# ProPrj_LED__2025-12-11-22-40-32.net
KiCad netlist of a schematic drawn in EasyEDA Pro
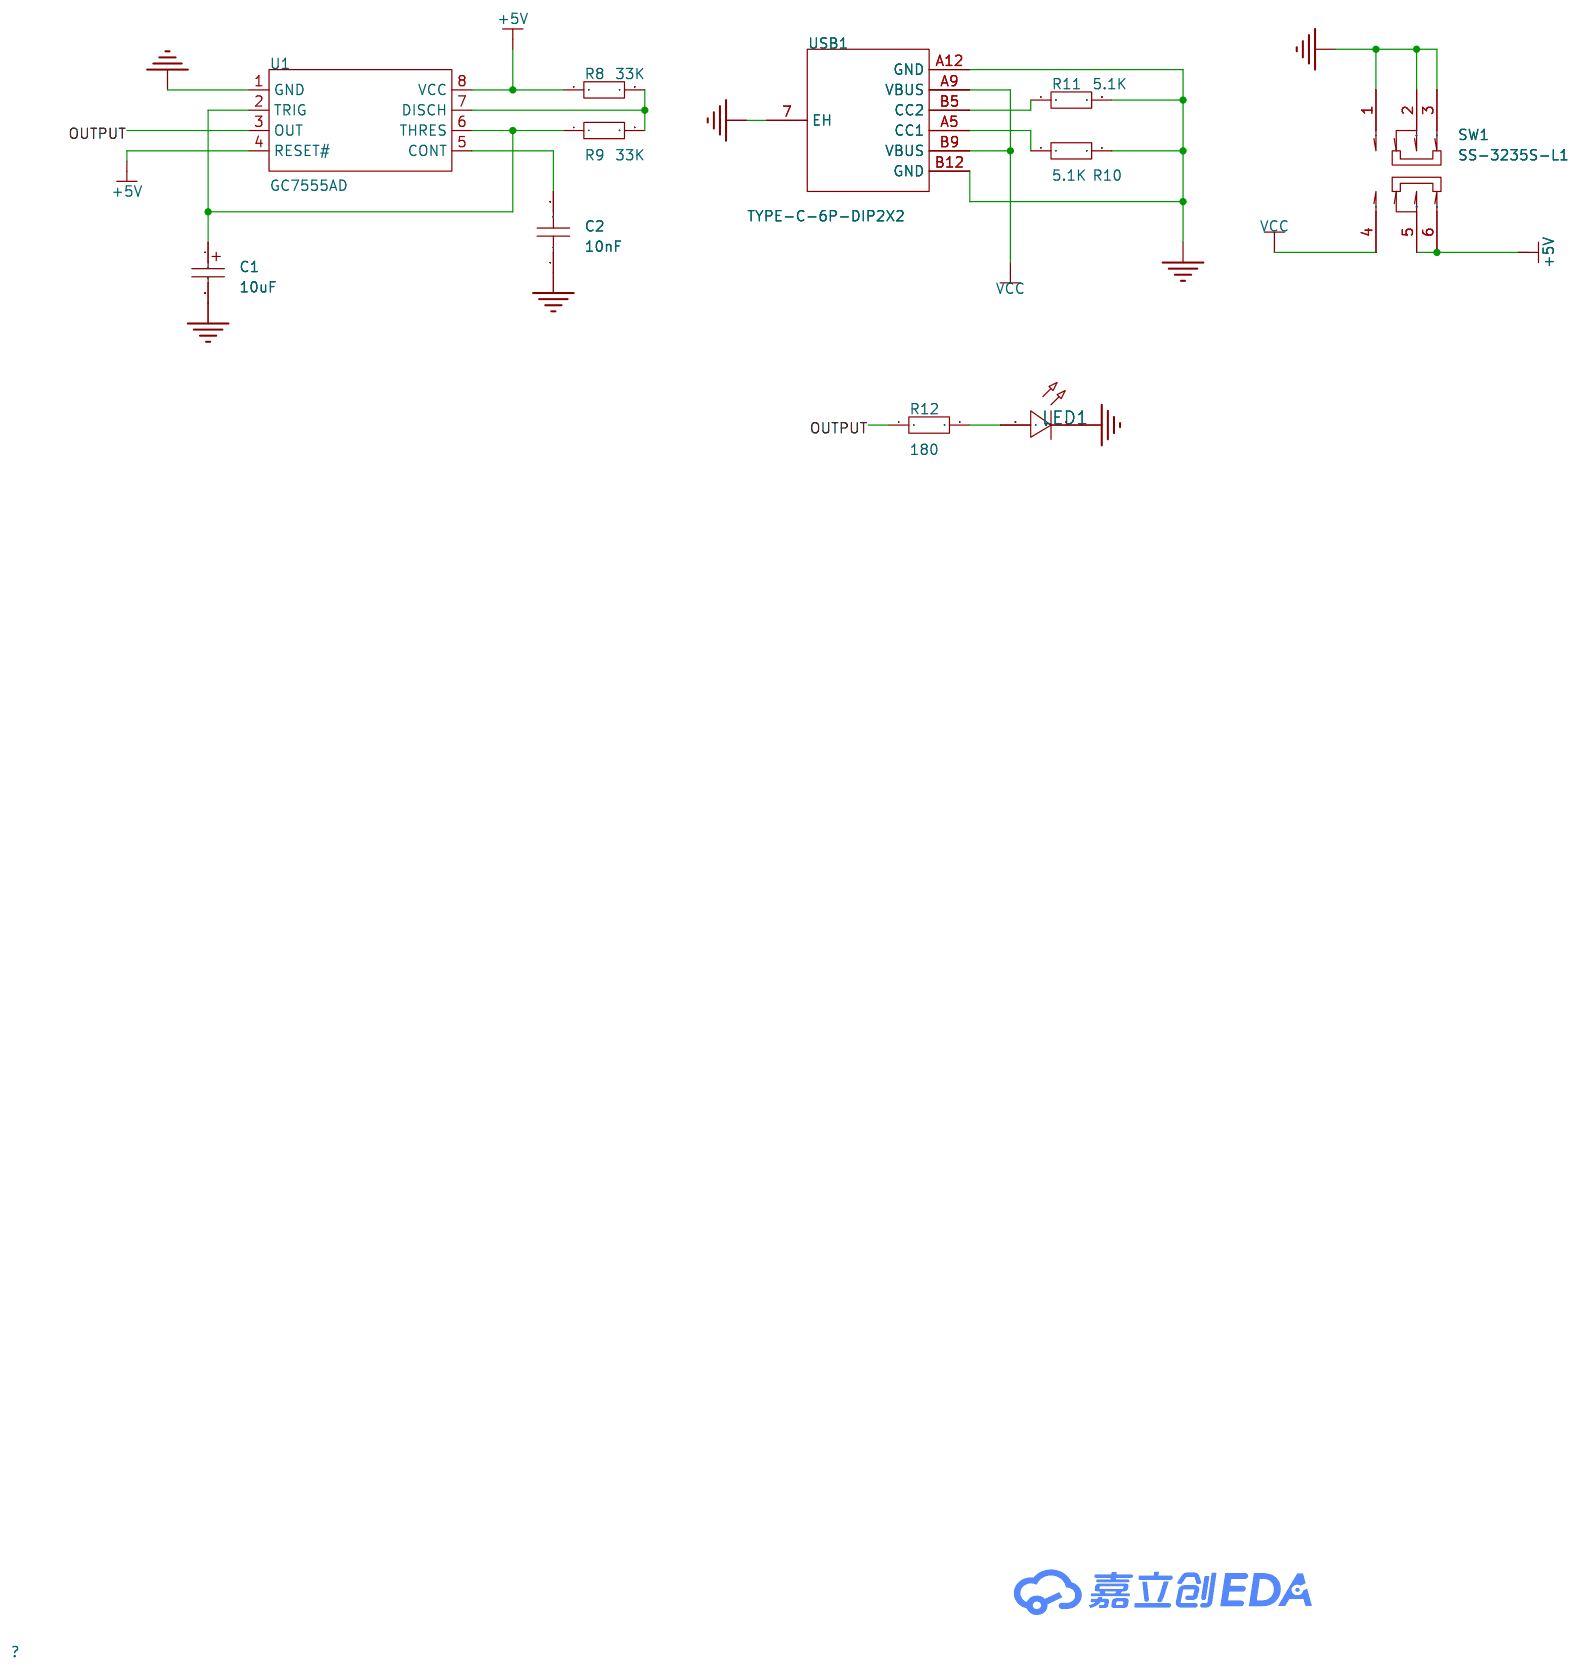
[diagram p0: schematic sheet]

(export (version "E")
  (design (tool "Eeschema 10.0.6"))
  (components
    (comp (ref "C1")
      (value "10uF")
      (footprint "easyedapro:C_Ele_SMD_3x5.4mm")
      (libsource (lib "easyedapro") (part "CAP"))
    )
    (comp (ref "C2")
      (value "10nF")
      (footprint "easyedapro:C0603")
      (libsource (lib "easyedapro") (part "Capacitance"))
    )
    (comp (ref "LED1")
      (value "~")
      (footprint "easyedapro:LED_0603")
      (libsource (lib "easyedapro") (part "LED_R"))
    )
    (comp (ref "R8") (value "33K") (footprint "easyedapro:R0805") (libsource (lib "easyedapro") (part "电阻")))
    (comp (ref "R9") (value "33K") (footprint "easyedapro:R0805") (libsource (lib "easyedapro") (part "电阻")))
    (comp (ref "R10")
      (value "5.1K")
      (footprint "easyedapro:R0805")
      (libsource (lib "easyedapro") (part "电阻"))
    )
    (comp (ref "R11")
      (value "5.1K")
      (footprint "easyedapro:R0805")
      (libsource (lib "easyedapro") (part "电阻"))
    )
    (comp (ref "R12") (value "180") (footprint "easyedapro:R0805") (libsource (lib "easyedapro") (part "电阻")))
    (comp (ref "SW1")
      (value "SS-3235S-L1")
      (footprint "easyedapro:SW-SMD_SS-3235S-LX")
      (description "电路结构:双刀双掷;安装方式:卧贴;开关颜色:黑色;额定电流:50mA;额定电压:12V;工作寿命:1万次;")
      (fields (field (name "Manufacturer") "XKB Connection(中国星坤)"))
      (libsource (lib "easyedapro") (part "SS-3235S-L1"))
    )
    (comp (ref "U1")
      (value "GC7555AD")
      (footprint "easyedapro:PDIP-8_L9.5-W6.4-P2.54-LS7.6-BL")
      (description "通用计时器：时基电路；计时；脉冲产生；满足用户（至少工业级）自主可控的需求。")
      (fields (field (name "Manufacturer") "Sungine(双竞集成)"))
      (libsource (lib "easyedapro") (part "GC7555AD"))
    )
    (comp (ref "USB1")
      (value "TYPE-C-6P-DIP2X2")
      (footprint "easyedapro:TYPE-C-SMD_TYPE-C-6P")
      (libsource (lib "easyedapro") (part "TYPE-C-6P-DIP2X2"))
    )
  )
  (nets
    (net (code "1") (name "+5V") (class "Default")
      (node (ref "R8") (pin "1") (pinfunction "1_1") (pintype "input"))
      (node (ref "SW1") (pin "5") (pinfunction "5_5") (pintype "unspecified"))
      (node (ref "SW1") (pin "6") (pinfunction "6_6") (pintype "unspecified"))
      (node (ref "U1") (pin "4") (pinfunction "RESET#_4") (pintype "unspecified"))
      (node (ref "U1") (pin "8") (pinfunction "VCC_8") (pintype "unspecified"))
    )
    (net (code "2") (name "/OUTPUT") (class "Default")
      (node (ref "R12") (pin "1") (pinfunction "1_1") (pintype "input"))
      (node (ref "U1") (pin "3") (pinfunction "OUT_3") (pintype "unspecified"))
    )
    (net (code "3") (name "GND") (class "Default")
      (node (ref "C1") (pin "2") (pinfunction "2_2") (pintype "input"))
      (node (ref "C2") (pin "1") (pinfunction "1_1") (pintype "input"))
      (node (ref "LED1") (pin "1") (pinfunction "C_1") (pintype "input"))
      (node (ref "R10") (pin "2") (pinfunction "2_2") (pintype "input"))
      (node (ref "R11") (pin "2") (pinfunction "2_2") (pintype "input"))
      (node (ref "SW1") (pin "1") (pinfunction "1_1") (pintype "unspecified"))
      (node (ref "SW1") (pin "2") (pinfunction "2_2") (pintype "unspecified"))
      (node (ref "SW1") (pin "3") (pinfunction "3_3") (pintype "unspecified"))
      (node (ref "U1") (pin "1") (pinfunction "GND_1") (pintype "unspecified"))
      (node (ref "USB1") (pin "7") (pinfunction "EH_7") (pintype "unspecified"))
      (node (ref "USB1") (pin "A12") (pinfunction "GND_A12") (pintype "unspecified"))
      (node (ref "USB1") (pin "B12") (pinfunction "GND_B12") (pintype "unspecified"))
    )
    (net (code "4") (name "Net-(LED1-A)") (class "Default")
      (node (ref "LED1") (pin "2") (pinfunction "A_2") (pintype "input"))
      (node (ref "R12") (pin "2") (pinfunction "2_2") (pintype "input"))
    )
    (net (code "5") (name "Net-(U1-CONT)") (class "Default")
      (node (ref "C2") (pin "2") (pinfunction "2_2") (pintype "input"))
      (node (ref "U1") (pin "5") (pinfunction "CONT_5") (pintype "unspecified"))
    )
    (net (code "6") (name "Net-(U1-DISCH)") (class "Default")
      (node (ref "R8") (pin "2") (pinfunction "2_2") (pintype "input"))
      (node (ref "R9") (pin "2") (pinfunction "2_2") (pintype "input"))
      (node (ref "U1") (pin "7") (pinfunction "DISCH_7") (pintype "unspecified"))
    )
    (net (code "7") (name "Net-(U1-THRES)") (class "Default")
      (node (ref "C1") (pin "1") (pinfunction "1_1") (pintype "input"))
      (node (ref "R9") (pin "1") (pinfunction "1_1") (pintype "input"))
      (node (ref "U1") (pin "2") (pinfunction "TRIG_2") (pintype "unspecified"))
      (node (ref "U1") (pin "6") (pinfunction "THRES_6") (pintype "unspecified"))
    )
    (net (code "8") (name "Net-(USB1-CC1)") (class "Default")
      (node (ref "R10") (pin "1") (pinfunction "1_1") (pintype "input"))
      (node (ref "USB1") (pin "A5") (pinfunction "CC1_A5") (pintype "unspecified"))
    )
    (net (code "9") (name "Net-(USB1-CC2)") (class "Default")
      (node (ref "R11") (pin "1") (pinfunction "1_1") (pintype "input"))
      (node (ref "USB1") (pin "B5") (pinfunction "CC2_B5") (pintype "unspecified"))
    )
    (net (code "10") (name "VCC") (class "Default")
      (node (ref "SW1") (pin "4") (pinfunction "4_4") (pintype "unspecified"))
      (node (ref "USB1") (pin "A9") (pinfunction "VBUS_A9") (pintype "unspecified"))
      (node (ref "USB1") (pin "B9") (pinfunction "VBUS_B9") (pintype "unspecified"))
    )
  )
)
